# Christmas_Keychain.net
KiCad netlist of a schematic drawn in Altium Designer
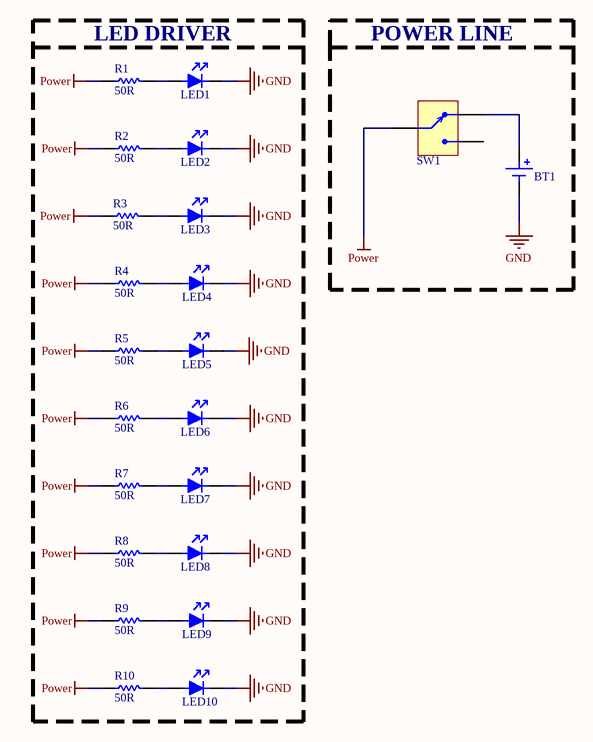
[diagram p0: Christmas Keychain.SchDoc]

(export (version "E")
  (design (tool "Eeschema 10.0.6"))
  (components
    (comp (ref "BT1")
      (value "BS-7")
      (footprint "BATTERY HOLDER")
      (description "BATTERY HOLDER 20MM TH")
      (fields
        (field (name "MANUFACTURER") "Wurth Electronics")
        (field (name "MANUFACTURER PART NUMBER") "150060BS75000")
      )
      (libsource (lib "Christmas Keychain") (part "BATTERY HOLDER TH"))
    )
    (comp (ref "LED1")
      (value "151031SS06000")
      (footprint "RED LED")
      (description "LED RED 3MM ROUND TH")
      (fields (field (name "MANUFACTURER") "Wurth Electronics"))
      (libsource (lib "Christmas Keychain") (part "RED LED TH"))
    )
    (comp (ref "LED2")
      (value "151031SS06000")
      (footprint "RED LED")
      (description "LED RED 3MM ROUND TH")
      (fields (field (name "MANUFACTURER") "Wurth Electronics"))
      (libsource (lib "Christmas Keychain") (part "RED LED TH"))
    )
    (comp (ref "LED3")
      (value "151031SS06000")
      (footprint "RED LED")
      (description "LED RED 3MM ROUND TH")
      (fields (field (name "MANUFACTURER") "Wurth Electronics"))
      (libsource (lib "Christmas Keychain") (part "RED LED TH"))
    )
    (comp (ref "LED4")
      (value "151031SS06000")
      (footprint "RED LED")
      (description "LED RED 3MM ROUND TH")
      (fields (field (name "MANUFACTURER") "Wurth Electronics"))
      (libsource (lib "Christmas Keychain") (part "RED LED TH"))
    )
    (comp (ref "LED5")
      (value "151031SS06000")
      (footprint "RED LED")
      (description "LED RED 3MM ROUND TH")
      (fields (field (name "MANUFACTURER") "Wurth Electronics"))
      (libsource (lib "Christmas Keychain") (part "RED LED TH"))
    )
    (comp (ref "LED6")
      (value "151031SS06000")
      (footprint "RED LED")
      (description "LED RED 3MM ROUND TH")
      (fields (field (name "MANUFACTURER") "Wurth Electronics"))
      (libsource (lib "Christmas Keychain") (part "RED LED TH"))
    )
    (comp (ref "LED7")
      (value "151031SS06000")
      (footprint "RED LED")
      (description "LED RED 3MM ROUND TH")
      (fields (field (name "MANUFACTURER") "Wurth Electronics"))
      (libsource (lib "Christmas Keychain") (part "RED LED TH"))
    )
    (comp (ref "LED8")
      (value "151031SS06000")
      (footprint "RED LED")
      (description "LED RED 3MM ROUND TH")
      (fields (field (name "MANUFACTURER") "Wurth Electronics"))
      (libsource (lib "Christmas Keychain") (part "RED LED TH"))
    )
    (comp (ref "LED9")
      (value "151031SS06000")
      (footprint "RED LED")
      (description "LED RED 3MM ROUND TH")
      (fields (field (name "MANUFACTURER") "Wurth Electronics"))
      (libsource (lib "Christmas Keychain") (part "RED LED TH"))
    )
    (comp (ref "LED10")
      (value "151031SS06000")
      (footprint "RED LED")
      (description "LED RED 3MM ROUND TH")
      (fields (field (name "MANUFACTURER") "Wurth Electronics"))
      (libsource (lib "Christmas Keychain") (part "RED LED TH"))
    )
    (comp (ref "R1")
      (value "50R")
      (footprint "RES 0805")
      (description "RES 50 OHM 1% 1/8W 0805")
      (fields
        (field (name "MANUFACTURER") "KOA Speer")
        (field (name "MANUFACTURER PART NUMBER") "RK73B2ATTD101J")
      )
      (libsource (lib "Christmas Keychain") (part "RES 50 OHM 0805 SMD"))
    )
    (comp (ref "R2")
      (value "50R")
      (footprint "RES 0805")
      (description "RES 50 OHM 1% 1/8W 0805")
      (fields
        (field (name "MANUFACTURER") "KOA Speer")
        (field (name "MANUFACTURER PART NUMBER") "RK73B2ATTD101J")
      )
      (libsource (lib "Christmas Keychain") (part "RES 50 OHM 0805 SMD"))
    )
    (comp (ref "R3")
      (value "50R")
      (footprint "RES 0805")
      (description "RES 50 OHM 1% 1/8W 0805")
      (fields
        (field (name "MANUFACTURER") "KOA Speer")
        (field (name "MANUFACTURER PART NUMBER") "RK73B2ATTD101J")
      )
      (libsource (lib "Christmas Keychain") (part "RES 50 OHM 0805 SMD"))
    )
    (comp (ref "R4")
      (value "50R")
      (footprint "RES 0805")
      (description "RES 50 OHM 1% 1/8W 0805")
      (fields
        (field (name "MANUFACTURER") "KOA Speer")
        (field (name "MANUFACTURER PART NUMBER") "RK73B2ATTD101J")
      )
      (libsource (lib "Christmas Keychain") (part "RES 50 OHM 0805 SMD"))
    )
    (comp (ref "R5")
      (value "50R")
      (footprint "RES 0805")
      (description "RES 50 OHM 1% 1/8W 0805")
      (fields
        (field (name "MANUFACTURER") "KOA Speer")
        (field (name "MANUFACTURER PART NUMBER") "RK73B2ATTD101J")
      )
      (libsource (lib "Christmas Keychain") (part "RES 50 OHM 0805 SMD"))
    )
    (comp (ref "R6")
      (value "50R")
      (footprint "RES 0805")
      (description "RES 50 OHM 1% 1/8W 0805")
      (fields
        (field (name "MANUFACTURER") "KOA Speer")
        (field (name "MANUFACTURER PART NUMBER") "RK73B2ATTD101J")
      )
      (libsource (lib "Christmas Keychain") (part "RES 50 OHM 0805 SMD"))
    )
    (comp (ref "R7")
      (value "50R")
      (footprint "RES 0805")
      (description "RES 50 OHM 1% 1/8W 0805")
      (fields
        (field (name "MANUFACTURER") "KOA Speer")
        (field (name "MANUFACTURER PART NUMBER") "RK73B2ATTD101J")
      )
      (libsource (lib "Christmas Keychain") (part "RES 50 OHM 0805 SMD"))
    )
    (comp (ref "R8")
      (value "50R")
      (footprint "RES 0805")
      (description "RES 50 OHM 1% 1/8W 0805")
      (fields
        (field (name "MANUFACTURER") "KOA Speer")
        (field (name "MANUFACTURER PART NUMBER") "RK73B2ATTD101J")
      )
      (libsource (lib "Christmas Keychain") (part "RES 50 OHM 0805 SMD"))
    )
    (comp (ref "R9")
      (value "50R")
      (footprint "RES 0805")
      (description "RES 50 OHM 1% 1/8W 0805")
      (fields
        (field (name "MANUFACTURER") "KOA Speer")
        (field (name "MANUFACTURER PART NUMBER") "RK73B2ATTD101J")
      )
      (libsource (lib "Christmas Keychain") (part "RES 50 OHM 0805 SMD"))
    )
    (comp (ref "R10")
      (value "50R")
      (footprint "RES 0805")
      (description "RES 50 OHM 1% 1/8W 0805")
      (fields
        (field (name "MANUFACTURER") "KOA Speer")
        (field (name "MANUFACTURER PART NUMBER") "RK73B2ATTD101J")
      )
      (libsource (lib "Christmas Keychain") (part "RES 50 OHM 0805 SMD"))
    )
    (comp (ref "SW1")
      (value "450404015514")
      (footprint "SLIDE SWITCH")
      (description "SLIDE SWITCH SMD 0.3A 5V")
      (fields (field (name "MANUFACTURER") "Wurth Electronics"))
      (libsource (lib "Christmas Keychain") (part "SLIDE SWITCH SMD"))
    )
  )
  (nets
    (net (code "1") (name "GND") (class "Default")
      (node (ref "BT1") (pin "2") (pintype "passive"))
      (node (ref "LED1") (pin "2") (pintype "passive"))
      (node (ref "LED10") (pin "2") (pintype "passive"))
      (node (ref "LED2") (pin "2") (pintype "passive"))
      (node (ref "LED3") (pin "2") (pintype "passive"))
      (node (ref "LED4") (pin "2") (pintype "passive"))
      (node (ref "LED5") (pin "2") (pintype "passive"))
      (node (ref "LED6") (pin "2") (pintype "passive"))
      (node (ref "LED7") (pin "2") (pintype "passive"))
      (node (ref "LED8") (pin "2") (pintype "passive"))
      (node (ref "LED9") (pin "2") (pintype "passive"))
    )
    (net (code "2") (name "Net-(BT1-Pad1)") (class "Default")
      (node (ref "BT1") (pin "1") (pintype "passive"))
      (node (ref "SW1") (pin "1") (pinfunction "1_1") (pintype "passive"))
    )
    (net (code "3") (name "Net-(LED1-Pad1)") (class "Default")
      (node (ref "LED1") (pin "1") (pintype "passive"))
      (node (ref "R1") (pin "2") (pintype "passive"))
    )
    (net (code "4") (name "Net-(LED2-Pad1)") (class "Default")
      (node (ref "LED2") (pin "1") (pintype "passive"))
      (node (ref "R2") (pin "2") (pintype "passive"))
    )
    (net (code "5") (name "Net-(LED3-Pad1)") (class "Default")
      (node (ref "LED3") (pin "1") (pintype "passive"))
      (node (ref "R3") (pin "2") (pintype "passive"))
    )
    (net (code "6") (name "Net-(LED4-Pad1)") (class "Default")
      (node (ref "LED4") (pin "1") (pintype "passive"))
      (node (ref "R4") (pin "2") (pintype "passive"))
    )
    (net (code "7") (name "Net-(LED5-Pad1)") (class "Default")
      (node (ref "LED5") (pin "1") (pintype "passive"))
      (node (ref "R5") (pin "2") (pintype "passive"))
    )
    (net (code "8") (name "Net-(LED6-Pad1)") (class "Default")
      (node (ref "LED6") (pin "1") (pintype "passive"))
      (node (ref "R6") (pin "2") (pintype "passive"))
    )
    (net (code "9") (name "Net-(LED7-Pad1)") (class "Default")
      (node (ref "LED7") (pin "1") (pintype "passive"))
      (node (ref "R7") (pin "2") (pintype "passive"))
    )
    (net (code "10") (name "Net-(LED8-Pad1)") (class "Default")
      (node (ref "LED8") (pin "1") (pintype "passive"))
      (node (ref "R8") (pin "2") (pintype "passive"))
    )
    (net (code "11") (name "Net-(LED9-Pad1)") (class "Default")
      (node (ref "LED9") (pin "1") (pintype "passive"))
      (node (ref "R9") (pin "2") (pintype "passive"))
    )
    (net (code "12") (name "Net-(LED10-Pad1)") (class "Default")
      (node (ref "LED10") (pin "1") (pintype "passive"))
      (node (ref "R10") (pin "2") (pintype "passive"))
    )
    (net (code "13") (name "Power") (class "Default")
      (node (ref "R1") (pin "1") (pintype "passive"))
      (node (ref "R10") (pin "1") (pintype "passive"))
      (node (ref "R2") (pin "1") (pintype "passive"))
      (node (ref "R3") (pin "1") (pintype "passive"))
      (node (ref "R4") (pin "1") (pintype "passive"))
      (node (ref "R5") (pin "1") (pintype "passive"))
      (node (ref "R6") (pin "1") (pintype "passive"))
      (node (ref "R7") (pin "1") (pintype "passive"))
      (node (ref "R8") (pin "1") (pintype "passive"))
      (node (ref "R9") (pin "1") (pintype "passive"))
      (node (ref "SW1") (pin "2") (pinfunction "2_2") (pintype "passive"))
    )
    (net (code "14") (name "unconnected-(SW1-Pad3)") (class "Default")
      (node (ref "SW1") (pin "3") (pinfunction "3_3") (pintype "passive"))
    )
  )
)
